# FE.net
KiCad netlist of a schematic drawn in Altium Designer
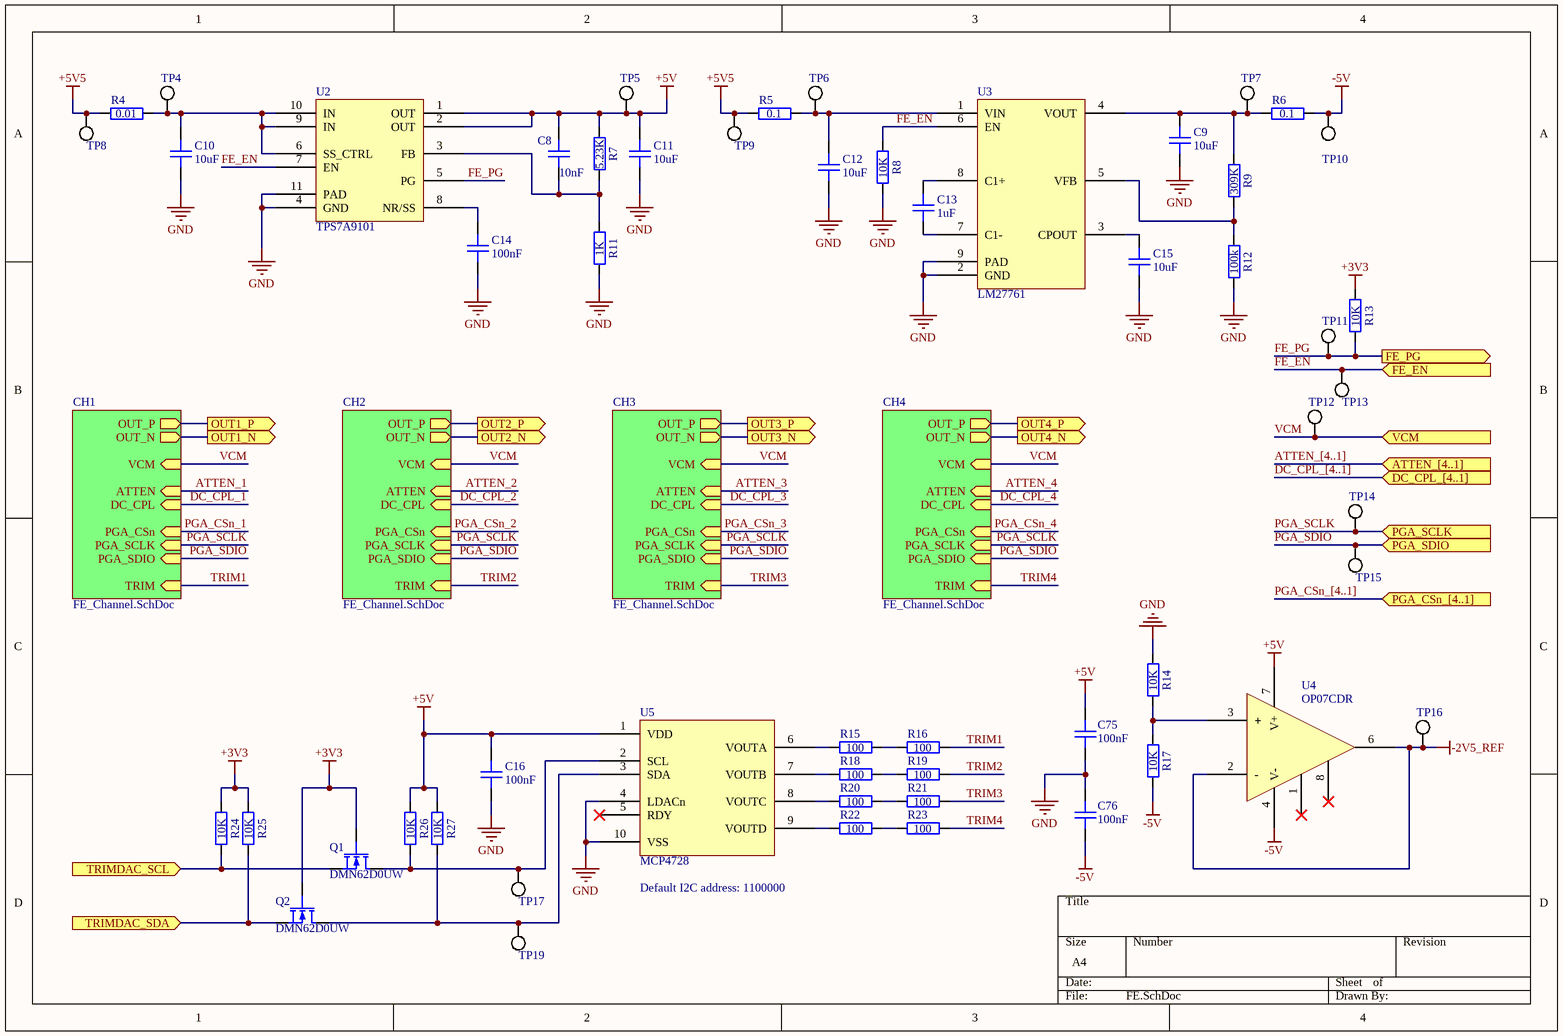
[diagram p0: FE.SchDoc]

(export (version "E")
  (design (tool "Eeschema 10.0.6"))
  (components
    (comp (ref "C8")
      (value "10nF")
      (footprint "GEN_C_0402")
      (libsource (lib "DSO") (part "CAP 10nF 50V X7R 0402"))
    )
    (comp (ref "C9")
      (value "10uF")
      (footprint "GEN_C_0603")
      (libsource (lib "DSO") (part "CAP 10uF 10V X5R 0603"))
    )
    (comp (ref "C10")
      (value "10uF")
      (footprint "GEN_C_0603")
      (libsource (lib "DSO") (part "CAP 10uF 10V X5R 0603"))
    )
    (comp (ref "C11")
      (value "10uF")
      (footprint "GEN_C_0603")
      (libsource (lib "DSO") (part "CAP 10uF 10V X5R 0603"))
    )
    (comp (ref "C12")
      (value "10uF")
      (footprint "GEN_C_0603")
      (libsource (lib "DSO") (part "CAP 10uF 10V X5R 0603"))
    )
    (comp (ref "C13")
      (value "1uF")
      (footprint "GEN_C_0402")
      (libsource (lib "DSO") (part "CAP 1uF 25V X5R 0402"))
    )
    (comp (ref "C14")
      (value "100nF")
      (footprint "GEN_C_0402")
      (libsource (lib "DSO") (part "CAP 100nF 16V X7R 0402"))
    )
    (comp (ref "C15")
      (value "10uF")
      (footprint "GEN_C_0603")
      (libsource (lib "DSO") (part "CAP 10uF 10V X5R 0603"))
    )
    (comp (ref "C16")
      (value "100nF")
      (footprint "GEN_C_0402")
      (libsource (lib "DSO") (part "CAP 100nF 16V X7R 0402"))
    )
    (comp (ref "C75")
      (value "100nF")
      (footprint "GEN_C_0402")
      (libsource (lib "DSO") (part "CAP 100nF 16V X7R 0402"))
    )
    (comp (ref "C76")
      (value "100nF")
      (footprint "GEN_C_0402")
      (libsource (lib "DSO") (part "CAP 100nF 16V X7R 0402"))
    )
    (comp (ref "Q1")
      (value "DMN62D0UW")
      (footprint "GEN_SOT_323")
      (libsource (lib "DSO") (part "NMOS DMN62D0UW"))
    )
    (comp (ref "Q2")
      (value "DMN62D0UW")
      (footprint "GEN_SOT_323")
      (libsource (lib "DSO") (part "NMOS DMN62D0UW"))
    )
    (comp (ref "R4")
      (value "0.01")
      (footprint "GEN_R_0603")
      (fields (field (name "TOLERANCE") "1%"))
      (libsource (lib "DSO") (part "RES 0.01 OHM 1% 1/4W 0603"))
    )
    (comp (ref "R5")
      (value "0.1")
      (footprint "GEN_R_0402")
      (fields (field (name "TOLERANCE") "1%"))
      (libsource (lib "DSO") (part "RES 0.1 OHM 1% 1/6W 0402"))
    )
    (comp (ref "R6")
      (value "0.1")
      (footprint "GEN_R_0402")
      (fields (field (name "TOLERANCE") "1%"))
      (libsource (lib "DSO") (part "RES 0.1 OHM 1% 1/6W 0402"))
    )
    (comp (ref "R7")
      (value "5.23K")
      (footprint "GEN_R_0402")
      (fields (field (name "TOLERANCE") "1%"))
      (libsource (lib "DSO") (part "RES 5.23K OHM 1% 1/16W 0402"))
    )
    (comp (ref "R8")
      (value "10K")
      (footprint "GEN_R_0402")
      (fields (field (name "TOLERANCE") "1%"))
      (libsource (lib "DSO") (part "RES 10K OHM 1% 1/10W 0402"))
    )
    (comp (ref "R9")
      (value "309K")
      (footprint "GEN_R_0402")
      (fields (field (name "TOLERANCE") "1%"))
      (libsource (lib "DSO") (part "RES 309K OHM 1% 1/16W 0402"))
    )
    (comp (ref "R11")
      (value "1K")
      (footprint "GEN_R_0402")
      (fields (field (name "TOLERANCE") "1%"))
      (libsource (lib "DSO") (part "RES 1K OHM 1% 1/10W 0402"))
    )
    (comp (ref "R12")
      (value "100k")
      (footprint "GEN_R_0402")
      (fields (field (name "TOLERANCE") "1%"))
      (libsource (lib "DSO") (part "RES 100K OHM 1% 1/10W 0402"))
    )
    (comp (ref "R13")
      (value "10K")
      (footprint "GEN_R_0402")
      (fields (field (name "TOLERANCE") "1%"))
      (libsource (lib "DSO") (part "RES 10K OHM 1% 1/10W 0402"))
    )
    (comp (ref "R14")
      (value "10K")
      (footprint "GEN_R_0402")
      (fields (field (name "TOLERANCE") "1%"))
      (libsource (lib "") (part "RES 10K OHM 1% 1/10W 0402_1"))
    )
    (comp (ref "R15")
      (value "100")
      (footprint "GEN_R_0402")
      (fields (field (name "TOLERANCE") "1%"))
      (libsource (lib "DSO") (part "RES 100 OHM 1% 1/10W 0402"))
    )
    (comp (ref "R16")
      (value "100")
      (footprint "GEN_R_0402")
      (fields (field (name "TOLERANCE") "1%"))
      (libsource (lib "DSO") (part "RES 100 OHM 1% 1/10W 0402"))
    )
    (comp (ref "R17")
      (value "10K")
      (footprint "GEN_R_0402")
      (fields (field (name "TOLERANCE") "1%"))
      (libsource (lib "") (part "RES 10K OHM 1% 1/10W 0402_1"))
    )
    (comp (ref "R18")
      (value "100")
      (footprint "GEN_R_0402")
      (fields (field (name "TOLERANCE") "1%"))
      (libsource (lib "DSO") (part "RES 100 OHM 1% 1/10W 0402"))
    )
    (comp (ref "R19")
      (value "100")
      (footprint "GEN_R_0402")
      (fields (field (name "TOLERANCE") "1%"))
      (libsource (lib "DSO") (part "RES 100 OHM 1% 1/10W 0402"))
    )
    (comp (ref "R20")
      (value "100")
      (footprint "GEN_R_0402")
      (fields (field (name "TOLERANCE") "1%"))
      (libsource (lib "DSO") (part "RES 100 OHM 1% 1/10W 0402"))
    )
    (comp (ref "R21")
      (value "100")
      (footprint "GEN_R_0402")
      (fields (field (name "TOLERANCE") "1%"))
      (libsource (lib "DSO") (part "RES 100 OHM 1% 1/10W 0402"))
    )
    (comp (ref "R22")
      (value "100")
      (footprint "GEN_R_0402")
      (fields (field (name "TOLERANCE") "1%"))
      (libsource (lib "DSO") (part "RES 100 OHM 1% 1/10W 0402"))
    )
    (comp (ref "R23")
      (value "100")
      (footprint "GEN_R_0402")
      (fields (field (name "TOLERANCE") "1%"))
      (libsource (lib "DSO") (part "RES 100 OHM 1% 1/10W 0402"))
    )
    (comp (ref "R24")
      (value "10K")
      (footprint "GEN_R_0402")
      (fields (field (name "TOLERANCE") "1%"))
      (libsource (lib "DSO") (part "RES 10K OHM 1% 1/10W 0402"))
    )
    (comp (ref "R25")
      (value "10K")
      (footprint "GEN_R_0402")
      (fields (field (name "TOLERANCE") "1%"))
      (libsource (lib "DSO") (part "RES 10K OHM 1% 1/10W 0402"))
    )
    (comp (ref "R26")
      (value "10K")
      (footprint "GEN_R_0402")
      (fields (field (name "TOLERANCE") "1%"))
      (libsource (lib "DSO") (part "RES 10K OHM 1% 1/10W 0402"))
    )
    (comp (ref "R27")
      (value "10K")
      (footprint "GEN_R_0402")
      (fields (field (name "TOLERANCE") "1%"))
      (libsource (lib "DSO") (part "RES 10K OHM 1% 1/10W 0402"))
    )
    (comp (ref "TP4") (value "PCB") (footprint "GEN_TP_PCB") (libsource (lib "DSO") (part "TP PCB 1mm")))
    (comp (ref "TP5") (value "PCB") (footprint "GEN_TP_PCB") (libsource (lib "DSO") (part "TP PCB 1mm")))
    (comp (ref "TP6") (value "PCB") (footprint "GEN_TP_PCB") (libsource (lib "DSO") (part "TP PCB 1mm")))
    (comp (ref "TP7") (value "PCB") (footprint "GEN_TP_PCB") (libsource (lib "DSO") (part "TP PCB 1mm")))
    (comp (ref "TP8") (value "PCB") (footprint "GEN_TP_PCB") (libsource (lib "DSO") (part "TP PCB 1mm")))
    (comp (ref "TP9") (value "PCB") (footprint "GEN_TP_PCB") (libsource (lib "DSO") (part "TP PCB 1mm")))
    (comp (ref "TP10") (value "PCB") (footprint "GEN_TP_PCB") (libsource (lib "DSO") (part "TP PCB 1mm")))
    (comp (ref "TP11") (value "PCB") (footprint "GEN_TP_PCB") (libsource (lib "DSO") (part "TP PCB 1mm")))
    (comp (ref "TP12") (value "PCB") (footprint "GEN_TP_PCB") (libsource (lib "DSO") (part "TP PCB 1mm")))
    (comp (ref "TP13") (value "PCB") (footprint "GEN_TP_PCB") (libsource (lib "DSO") (part "TP PCB 1mm")))
    (comp (ref "TP14") (value "PCB") (footprint "GEN_TP_PCB") (libsource (lib "DSO") (part "TP PCB 1mm")))
    (comp (ref "TP15") (value "PCB") (footprint "GEN_TP_PCB") (libsource (lib "DSO") (part "TP PCB 1mm")))
    (comp (ref "TP16") (value "PCB") (footprint "GEN_TP_PCB") (libsource (lib "DSO") (part "TP PCB 1mm")))
    (comp (ref "TP17") (value "PCB") (footprint "GEN_TP_PCB") (libsource (lib "DSO") (part "TP PCB 1mm")))
    (comp (ref "TP19") (value "PCB") (footprint "GEN_TP_PCB") (libsource (lib "DSO") (part "TP PCB 1mm")))
    (comp (ref "U2")
      (value "TPS7A9101")
      (footprint "TI_WSON10_DSK0010A")
      (libsource (lib "DSO") (part "IC LDO TPS7A9101"))
    )
    (comp (ref "U3")
      (value "LM27761")
      (footprint "TI_WSON8_DSG0008A")
      (libsource (lib "DSO") (part "IC CPUMP LM27761"))
    )
    (comp (ref "U4")
      (value "OP07CDR")
      (footprint "TI_SOIC8_D0008A")
      (libsource (lib "DSO") (part "IC OPAMP OP07CDR"))
    )
    (comp (ref "U5")
      (value "MCP4728")
      (footprint "MC_MSOP10_UN")
      (libsource (lib "DSO") (part "IC DAC QUAD MCP4728"))
    )
  )
  (nets
    (net (code "1") (name "+3V3") (class "Default")
      (node (ref "Q1") (pin "2") (pinfunction "G_2") (pintype "passive"))
      (node (ref "Q2") (pin "2") (pinfunction "G_2") (pintype "passive"))
      (node (ref "R13") (pin "2") (pinfunction "2_2") (pintype "passive"))
      (node (ref "R24") (pin "2") (pinfunction "2_2") (pintype "passive"))
      (node (ref "R25") (pin "2") (pinfunction "2_2") (pintype "passive"))
    )
    (net (code "2") (name "+5V") (class "Default")
      (node (ref "C11") (pin "2") (pinfunction "2_2") (pintype "passive"))
      (node (ref "C16") (pin "2") (pinfunction "2_2") (pintype "passive"))
      (node (ref "C75") (pin "1") (pinfunction "1_1") (pintype "passive"))
      (node (ref "C8") (pin "2") (pinfunction "2_2") (pintype "passive"))
      (node (ref "R26") (pin "2") (pinfunction "2_2") (pintype "passive"))
      (node (ref "R27") (pin "2") (pinfunction "2_2") (pintype "passive"))
      (node (ref "R7") (pin "2") (pinfunction "2_2") (pintype "passive"))
      (node (ref "TP5") (pin "1") (pinfunction "1_1") (pintype "passive"))
      (node (ref "U2") (pin "1") (pinfunction "OUT_1") (pintype "power_in"))
      (node (ref "U2") (pin "2") (pinfunction "OUT_2") (pintype "power_in"))
      (node (ref "U4") (pin "7") (pinfunction "V+_7") (pintype "passive"))
      (node (ref "U5") (pin "1") (pinfunction "VDD_1") (pintype "power_in"))
    )
    (net (code "3") (name "+5V5") (class "Default")
      (node (ref "R4") (pin "1") (pinfunction "1_1") (pintype "passive"))
      (node (ref "R5") (pin "1") (pinfunction "1_1") (pintype "passive"))
      (node (ref "TP8") (pin "1") (pinfunction "1_1") (pintype "passive"))
      (node (ref "TP9") (pin "1") (pinfunction "1_1") (pintype "passive"))
    )
    (net (code "4") (name "-2V5_REF") (class "Default")
      (node (ref "TP16") (pin "1") (pinfunction "1_1") (pintype "passive"))
      (node (ref "U4") (pin "2") (pinfunction "-_2") (pintype "passive"))
      (node (ref "U4") (pin "6") (pinfunction "OUT_6") (pintype "passive"))
    )
    (net (code "5") (name "-5V") (class "Default")
      (node (ref "C76") (pin "2") (pinfunction "2_2") (pintype "passive"))
      (node (ref "R17") (pin "1") (pinfunction "1_1") (pintype "passive"))
      (node (ref "R6") (pin "2") (pinfunction "2_2") (pintype "passive"))
      (node (ref "TP10") (pin "1") (pinfunction "1_1") (pintype "passive"))
      (node (ref "U4") (pin "4") (pinfunction "V-_4") (pintype "passive"))
    )
    (net (code "16") (name "/FE_EN") (class "Default")
      (node (ref "R8") (pin "2") (pinfunction "2_2") (pintype "passive"))
      (node (ref "TP13") (pin "1") (pinfunction "1_1") (pintype "passive"))
      (node (ref "U2") (pin "7") (pinfunction "EN_7") (pintype "passive"))
      (node (ref "U3") (pin "6") (pinfunction "EN_6") (pintype "passive"))
    )
    (net (code "17") (name "/FE_PG") (class "Default")
      (node (ref "R13") (pin "1") (pinfunction "1_1") (pintype "passive"))
      (node (ref "TP11") (pin "1") (pinfunction "1_1") (pintype "passive"))
      (node (ref "U2") (pin "5") (pinfunction "PG_5") (pintype "passive"))
    )
    (net (code "31") (name "/PGA_SCLK") (class "Default")
      (node (ref "TP14") (pin "1") (pinfunction "1_1") (pintype "passive"))
    )
    (net (code "32") (name "/PGA_SDIO") (class "Default")
      (node (ref "TP15") (pin "1") (pinfunction "1_1") (pintype "passive"))
    )
    (net (code "33") (name "/TRIM1") (class "Default")
      (node (ref "R16") (pin "1") (pinfunction "1_1") (pintype "passive"))
    )
    (net (code "34") (name "/TRIM2") (class "Default")
      (node (ref "R19") (pin "1") (pinfunction "1_1") (pintype "passive"))
    )
    (net (code "35") (name "/TRIM3") (class "Default")
      (node (ref "R21") (pin "1") (pinfunction "1_1") (pintype "passive"))
    )
    (net (code "36") (name "/TRIM4") (class "Default")
      (node (ref "R23") (pin "1") (pinfunction "1_1") (pintype "passive"))
    )
    (net (code "37") (name "/TRIMDAC_SCL") (class "Default")
      (node (ref "Q1") (pin "3") (pinfunction "S_3") (pintype "passive"))
      (node (ref "R24") (pin "1") (pinfunction "1_1") (pintype "passive"))
    )
    (net (code "38") (name "/TRIMDAC_SDA") (class "Default")
      (node (ref "Q2") (pin "3") (pinfunction "S_3") (pintype "passive"))
      (node (ref "R25") (pin "1") (pinfunction "1_1") (pintype "passive"))
    )
    (net (code "39") (name "/VCM") (class "Default")
      (node (ref "TP12") (pin "1") (pinfunction "1_1") (pintype "passive"))
    )
    (net (code "40") (name "GND") (class "Default")
      (node (ref "C10") (pin "1") (pinfunction "1_1") (pintype "passive"))
      (node (ref "C11") (pin "1") (pinfunction "1_1") (pintype "passive"))
      (node (ref "C12") (pin "1") (pinfunction "1_1") (pintype "passive"))
      (node (ref "C14") (pin "1") (pinfunction "1_1") (pintype "passive"))
      (node (ref "C15") (pin "1") (pinfunction "1_1") (pintype "passive"))
      (node (ref "C16") (pin "1") (pinfunction "1_1") (pintype "passive"))
      (node (ref "C75") (pin "2") (pinfunction "2_2") (pintype "passive"))
      (node (ref "C76") (pin "1") (pinfunction "1_1") (pintype "passive"))
      (node (ref "C9") (pin "1") (pinfunction "1_1") (pintype "passive"))
      (node (ref "R11") (pin "1") (pinfunction "1_1") (pintype "passive"))
      (node (ref "R12") (pin "1") (pinfunction "1_1") (pintype "passive"))
      (node (ref "R14") (pin "2") (pinfunction "2_2") (pintype "passive"))
      (node (ref "R8") (pin "1") (pinfunction "1_1") (pintype "passive"))
      (node (ref "U2") (pin "11") (pinfunction "PAD_11") (pintype "passive"))
      (node (ref "U2") (pin "4") (pinfunction "GND_4") (pintype "power_in"))
      (node (ref "U3") (pin "2") (pinfunction "GND_2") (pintype "power_in"))
      (node (ref "U3") (pin "9") (pinfunction "PAD_9") (pintype "power_in"))
      (node (ref "U5") (pin "10") (pinfunction "VSS_10") (pintype "power_in"))
      (node (ref "U5") (pin "4") (pinfunction "LDACn_4") (pintype "passive"))
    )
    (net (code "41") (name "Net-(Q1-D)") (class "Default")
      (node (ref "Q1") (pin "1") (pinfunction "D_1") (pintype "passive"))
      (node (ref "R26") (pin "1") (pinfunction "1_1") (pintype "passive"))
      (node (ref "TP17") (pin "1") (pinfunction "1_1") (pintype "passive"))
      (node (ref "U5") (pin "2") (pinfunction "SCL_2") (pintype "passive"))
    )
    (net (code "42") (name "Net-(Q2-D)") (class "Default")
      (node (ref "Q2") (pin "1") (pinfunction "D_1") (pintype "passive"))
      (node (ref "R27") (pin "1") (pinfunction "1_1") (pintype "passive"))
      (node (ref "TP19") (pin "1") (pinfunction "1_1") (pintype "passive"))
      (node (ref "U5") (pin "3") (pinfunction "SDA_3") (pintype "passive"))
    )
    (net (code "43") (name "Net-(R15-Pad1)") (class "Default")
      (node (ref "R15") (pin "1") (pinfunction "1_1") (pintype "passive"))
      (node (ref "R16") (pin "2") (pinfunction "2_2") (pintype "passive"))
    )
    (net (code "44") (name "Net-(R18-Pad1)") (class "Default")
      (node (ref "R18") (pin "1") (pinfunction "1_1") (pintype "passive"))
      (node (ref "R19") (pin "2") (pinfunction "2_2") (pintype "passive"))
    )
    (net (code "45") (name "Net-(R20-Pad1)") (class "Default")
      (node (ref "R20") (pin "1") (pinfunction "1_1") (pintype "passive"))
      (node (ref "R21") (pin "2") (pinfunction "2_2") (pintype "passive"))
    )
    (net (code "46") (name "Net-(R22-Pad1)") (class "Default")
      (node (ref "R22") (pin "1") (pinfunction "1_1") (pintype "passive"))
      (node (ref "R23") (pin "2") (pinfunction "2_2") (pintype "passive"))
    )
    (net (code "47") (name "Net-(U2-FB)") (class "Default")
      (node (ref "C8") (pin "1") (pinfunction "1_1") (pintype "passive"))
      (node (ref "R11") (pin "2") (pinfunction "2_2") (pintype "passive"))
      (node (ref "R7") (pin "1") (pinfunction "1_1") (pintype "passive"))
      (node (ref "U2") (pin "3") (pinfunction "FB_3") (pintype "passive"))
    )
    (net (code "48") (name "Net-(U2-NR{slash}SS)") (class "Default")
      (node (ref "C14") (pin "2") (pinfunction "2_2") (pintype "passive"))
      (node (ref "U2") (pin "8") (pinfunction "NR/SS_8") (pintype "passive"))
    )
    (net (code "49") (name "Net-(U2-SS_CTRL)") (class "Default")
      (node (ref "C10") (pin "2") (pinfunction "2_2") (pintype "passive"))
      (node (ref "R4") (pin "2") (pinfunction "2_2") (pintype "passive"))
      (node (ref "TP4") (pin "1") (pinfunction "1_1") (pintype "passive"))
      (node (ref "U2") (pin "10") (pinfunction "IN_10") (pintype "power_in"))
      (node (ref "U2") (pin "6") (pinfunction "SS_CTRL_6") (pintype "passive"))
      (node (ref "U2") (pin "9") (pinfunction "IN_9") (pintype "power_in"))
    )
    (net (code "50") (name "Net-(U3-C1+)") (class "Default")
      (node (ref "C13") (pin "2") (pinfunction "2_2") (pintype "passive"))
      (node (ref "U3") (pin "8") (pinfunction "C1+_8") (pintype "passive"))
    )
    (net (code "51") (name "Net-(U3-C1-)") (class "Default")
      (node (ref "C13") (pin "1") (pinfunction "1_1") (pintype "passive"))
      (node (ref "U3") (pin "7") (pinfunction "C1-_7") (pintype "passive"))
    )
    (net (code "52") (name "Net-(U3-CPOUT)") (class "Default")
      (node (ref "C15") (pin "2") (pinfunction "2_2") (pintype "passive"))
      (node (ref "U3") (pin "3") (pinfunction "CPOUT_3") (pintype "passive"))
    )
    (net (code "53") (name "Net-(U3-VFB)") (class "Default")
      (node (ref "R12") (pin "2") (pinfunction "2_2") (pintype "passive"))
      (node (ref "R9") (pin "1") (pinfunction "1_1") (pintype "passive"))
      (node (ref "U3") (pin "5") (pinfunction "VFB_5") (pintype "passive"))
    )
    (net (code "54") (name "Net-(U3-VIN)") (class "Default")
      (node (ref "C12") (pin "2") (pinfunction "2_2") (pintype "passive"))
      (node (ref "R5") (pin "2") (pinfunction "2_2") (pintype "passive"))
      (node (ref "TP6") (pin "1") (pinfunction "1_1") (pintype "passive"))
      (node (ref "U3") (pin "1") (pinfunction "VIN_1") (pintype "power_in"))
    )
    (net (code "55") (name "Net-(U3-VOUT)") (class "Default")
      (node (ref "C9") (pin "2") (pinfunction "2_2") (pintype "passive"))
      (node (ref "R6") (pin "1") (pinfunction "1_1") (pintype "passive"))
      (node (ref "R9") (pin "2") (pinfunction "2_2") (pintype "passive"))
      (node (ref "TP7") (pin "1") (pinfunction "1_1") (pintype "passive"))
      (node (ref "U3") (pin "4") (pinfunction "VOUT_4") (pintype "power_in"))
    )
    (net (code "56") (name "Net-(U4-+)") (class "Default")
      (node (ref "R14") (pin "1") (pinfunction "1_1") (pintype "passive"))
      (node (ref "R17") (pin "2") (pinfunction "2_2") (pintype "passive"))
      (node (ref "U4") (pin "3") (pinfunction "+_3") (pintype "passive"))
    )
    (net (code "57") (name "Net-(U5-VOUTA)") (class "Default")
      (node (ref "R15") (pin "2") (pinfunction "2_2") (pintype "passive"))
      (node (ref "U5") (pin "6") (pinfunction "VOUTA_6") (pintype "passive"))
    )
    (net (code "58") (name "Net-(U5-VOUTB)") (class "Default")
      (node (ref "R18") (pin "2") (pinfunction "2_2") (pintype "passive"))
      (node (ref "U5") (pin "7") (pinfunction "VOUTB_7") (pintype "passive"))
    )
    (net (code "59") (name "Net-(U5-VOUTC)") (class "Default")
      (node (ref "R20") (pin "2") (pinfunction "2_2") (pintype "passive"))
      (node (ref "U5") (pin "8") (pinfunction "VOUTC_8") (pintype "passive"))
    )
    (net (code "60") (name "Net-(U5-VOUTD)") (class "Default")
      (node (ref "R22") (pin "2") (pinfunction "2_2") (pintype "passive"))
      (node (ref "U5") (pin "9") (pinfunction "VOUTD_9") (pintype "passive"))
    )
    (net (code "61") (name "unconnected-(U4-N1-Pad1)") (class "Default")
      (node (ref "U4") (pin "1") (pinfunction "N1_1") (pintype "passive+no_connect"))
    )
    (net (code "62") (name "unconnected-(U4-N2-Pad8)") (class "Default")
      (node (ref "U4") (pin "8") (pinfunction "N2_8") (pintype "passive+no_connect"))
    )
    (net (code "63") (name "unconnected-(U5-RDY-Pad5)") (class "Default")
      (node (ref "U5") (pin "5") (pinfunction "RDY_5") (pintype "passive+no_connect"))
    )
  )
)
